# openThermostatShield.net
KiCad netlist of a schematic drawn in EAGLE
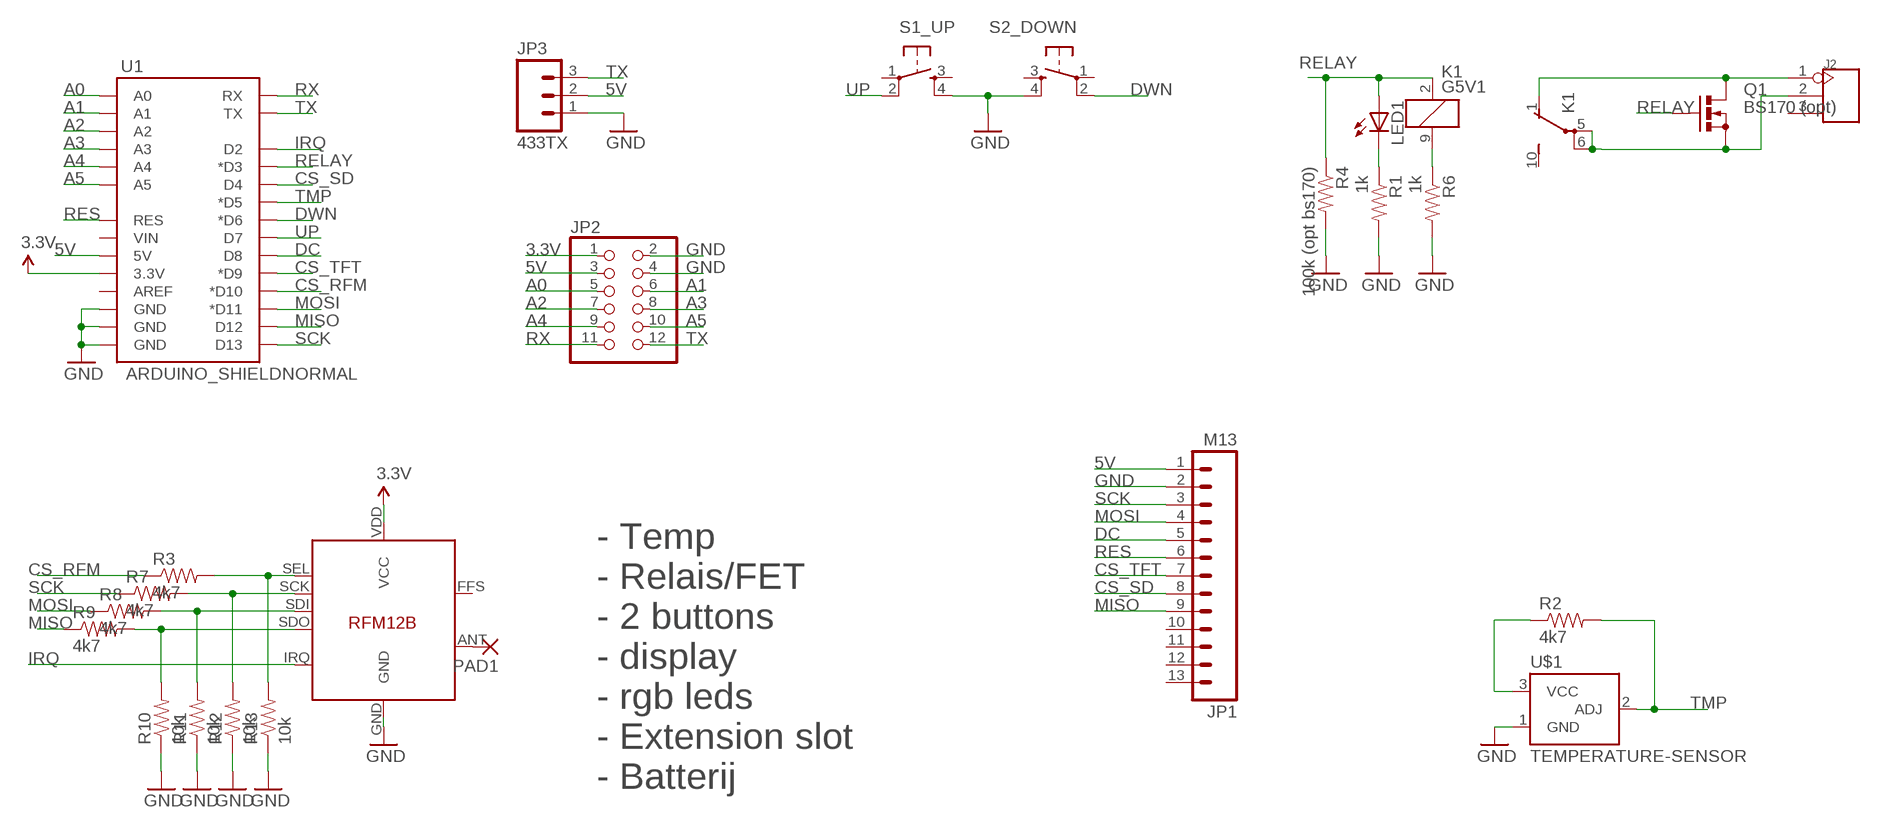
[diagram p0: schematic, sheet 1]

(export (version "E")
  (design (tool "Eeschema 10.0.6"))
  (components
    (comp (ref "J2")
      (value "SCREW-TERMINAL-3P'5.08'")
      (footprint "eagle-import:3P-5.08")
      (libsource (lib "eagle-import") (part "SCREW-TERMINAL-3P'5.08'"))
    )
    (comp (ref "JP1")
      (value "M13")
      (footprint "eagle-import:1X13")
      (libsource (lib "eagle-import") (part "M13"))
    )
    (comp (ref "JP2")
      (value "PINHD-2X6/90")
      (footprint "eagle-import:2X06_90")
      (libsource (lib "eagle-import") (part "PINHD-2X6/90"))
    )
    (comp (ref "JP3")
      (value "433TX")
      (footprint "eagle-import:MOLEX-1X3")
      (libsource (lib "eagle-import") (part "M03POLAR"))
    )
    (comp (ref "K1")
      (value "G5V1")
      (footprint "eagle-import:G5V1")
      (fields (field (name "MPN") "G5V-1-DC24"))
      (libsource (lib "eagle-import") (part "G5V1"))
    )
    (comp (ref "LED1")
      (value "LED-3MM-NO_SILK")
      (footprint "eagle-import:LED3MM-NS")
      (libsource (lib "eagle-import") (part "LED-3MM-NO_SILK"))
    )
    (comp (ref "PAD1")
      (value "1,6/0,8")
      (footprint "eagle-import:1,6_0,8")
      (libsource (lib "eagle-import") (part "1,6/0,8"))
    )
    (comp (ref "Q1")
      (value "BS170 (opt)")
      (footprint "eagle-import:SOT54E")
      (libsource (lib "eagle-import") (part "BS170"))
    )
    (comp (ref "R1")
      (value "1k")
      (footprint "eagle-import:AXIAL-0.3")
      (libsource (lib "eagle-import") (part "RESISTORAXIAL-0.3"))
    )
    (comp (ref "R2")
      (value "4k7")
      (footprint "eagle-import:AXIAL-0.3")
      (libsource (lib "eagle-import") (part "RESISTORAXIAL-0.3"))
    )
    (comp (ref "R3")
      (value "4k7")
      (footprint "eagle-import:AXIAL-0.3")
      (libsource (lib "eagle-import") (part "RESISTORAXIAL-0.3"))
    )
    (comp (ref "R4")
      (value "100k (opt bs170)")
      (footprint "eagle-import:AXIAL-0.3")
      (libsource (lib "eagle-import") (part "RESISTORAXIAL-0.3"))
    )
    (comp (ref "R6")
      (value "1k")
      (footprint "eagle-import:AXIAL-0.3")
      (libsource (lib "eagle-import") (part "RESISTORAXIAL-0.3"))
    )
    (comp (ref "R7")
      (value "4k7")
      (footprint "eagle-import:AXIAL-0.3")
      (libsource (lib "eagle-import") (part "RESISTORAXIAL-0.3"))
    )
    (comp (ref "R8")
      (value "4k7")
      (footprint "eagle-import:AXIAL-0.3")
      (libsource (lib "eagle-import") (part "RESISTORAXIAL-0.3"))
    )
    (comp (ref "R9")
      (value "4k7")
      (footprint "eagle-import:AXIAL-0.3")
      (libsource (lib "eagle-import") (part "RESISTORAXIAL-0.3"))
    )
    (comp (ref "R10")
      (value "10k")
      (footprint "eagle-import:AXIAL-0.3")
      (libsource (lib "eagle-import") (part "RESISTORAXIAL-0.3"))
    )
    (comp (ref "R11")
      (value "10k")
      (footprint "eagle-import:AXIAL-0.3")
      (libsource (lib "eagle-import") (part "RESISTORAXIAL-0.3"))
    )
    (comp (ref "R12")
      (value "10k")
      (footprint "eagle-import:AXIAL-0.3")
      (libsource (lib "eagle-import") (part "RESISTORAXIAL-0.3"))
    )
    (comp (ref "R13")
      (value "10k")
      (footprint "eagle-import:AXIAL-0.3")
      (libsource (lib "eagle-import") (part "RESISTORAXIAL-0.3"))
    )
    (comp (ref "S1_UP")
      (value "TAC_SWITCHPTH")
      (footprint "eagle-import:TACTILE-PTH")
      (libsource (lib "eagle-import") (part "TAC_SWITCHPTH"))
    )
    (comp (ref "S2_DOWN")
      (value "TAC_SWITCHPTH")
      (footprint "eagle-import:TACTILE-PTH")
      (libsource (lib "eagle-import") (part "TAC_SWITCHPTH"))
    )
    (comp (ref "U$1")
      (value "TEMPERATURE-SENSOR")
      (footprint "eagle-import:TO-92")
      (libsource (lib "eagle-import") (part "TEMPERATURE-SENSOR"))
    )
    (comp (ref "U$2")
      (value "RFM12B")
      (footprint "eagle-import:RFM12B")
      (libsource (lib "eagle-import") (part "RFM12B"))
    )
    (comp (ref "U1")
      (value "ARDUINO_SHIELDNORMAL")
      (footprint "eagle-import:DUEMILANOVE_SHIELD_5X5")
      (libsource (lib "eagle-import") (part "ARDUINO_SHIELDNORMAL"))
    )
  )
  (nets
    (net (code "1") (name "/5V") (class "Default")
      (node (ref "JP1") (pin "1") (pinfunction "1_1") (pintype "passive"))
      (node (ref "JP2") (pin "3") (pinfunction "3_3") (pintype "passive"))
      (node (ref "JP3") (pin "2") (pinfunction "2_2") (pintype "passive"))
      (node (ref "U1") (pin "5V") (pinfunction "5V_5V") (pintype "bidirectional"))
    )
    (net (code "2") (name "/A0") (class "Default")
      (node (ref "JP2") (pin "5") (pinfunction "5_5") (pintype "passive"))
      (node (ref "U1") (pin "A0") (pinfunction "A0_A0") (pintype "bidirectional"))
    )
    (net (code "3") (name "/A1") (class "Default")
      (node (ref "JP2") (pin "6") (pinfunction "6_6") (pintype "passive"))
      (node (ref "U1") (pin "A1") (pinfunction "A1_A1") (pintype "bidirectional"))
    )
    (net (code "4") (name "/A2") (class "Default")
      (node (ref "JP2") (pin "7") (pinfunction "7_7") (pintype "passive"))
      (node (ref "U1") (pin "A2") (pinfunction "A2_A2") (pintype "bidirectional"))
    )
    (net (code "5") (name "/A3") (class "Default")
      (node (ref "JP2") (pin "8") (pinfunction "8_8") (pintype "passive"))
      (node (ref "U1") (pin "A3") (pinfunction "A3_A3") (pintype "bidirectional"))
    )
    (net (code "6") (name "/A4") (class "Default")
      (node (ref "JP2") (pin "9") (pinfunction "9_9") (pintype "passive"))
      (node (ref "U1") (pin "A4") (pinfunction "A4_A4") (pintype "bidirectional"))
    )
    (net (code "7") (name "/A5") (class "Default")
      (node (ref "JP2") (pin "10") (pinfunction "10_10") (pintype "passive"))
      (node (ref "U1") (pin "A5") (pinfunction "A5_A5") (pintype "bidirectional"))
    )
    (net (code "8") (name "/CS_RFM") (class "Default")
      (node (ref "R3") (pin "P$1") (pinfunction "1_P$1") (pintype "passive"))
      (node (ref "U1") (pin "D10") (pinfunction "*D10_D10") (pintype "bidirectional"))
    )
    (net (code "9") (name "/CS_SD") (class "Default")
      (node (ref "JP1") (pin "8") (pinfunction "8_8") (pintype "passive"))
      (node (ref "U1") (pin "D4") (pinfunction "D4_D4") (pintype "bidirectional"))
    )
    (net (code "10") (name "/CS_TFT") (class "Default")
      (node (ref "JP1") (pin "7") (pinfunction "7_7") (pintype "passive"))
      (node (ref "U1") (pin "D9") (pinfunction "*D9_D9") (pintype "bidirectional"))
    )
    (net (code "11") (name "/DC") (class "Default")
      (node (ref "JP1") (pin "5") (pinfunction "5_5") (pintype "passive"))
      (node (ref "U1") (pin "D8") (pinfunction "D8_D8") (pintype "bidirectional"))
    )
    (net (code "12") (name "/DWN") (class "Default")
      (node (ref "S2_DOWN") (pin "2") (pinfunction "2_2") (pintype "passive"))
      (node (ref "U1") (pin "D6") (pinfunction "*D6_D6") (pintype "bidirectional"))
    )
    (net (code "13") (name "/IRQ") (class "Default")
      (node (ref "U$2") (pin "IRQ") (pinfunction "IRQ_IRQ") (pintype "open_collector"))
      (node (ref "U1") (pin "D2") (pinfunction "D2_D2") (pintype "bidirectional"))
    )
    (net (code "14") (name "/MISO") (class "Default")
      (node (ref "JP1") (pin "9") (pinfunction "9_9") (pintype "passive"))
      (node (ref "R9") (pin "P$1") (pinfunction "1_P$1") (pintype "passive"))
      (node (ref "U1") (pin "D12") (pinfunction "D12_D12") (pintype "bidirectional"))
    )
    (net (code "15") (name "/MOSI") (class "Default")
      (node (ref "JP1") (pin "4") (pinfunction "4_4") (pintype "passive"))
      (node (ref "R8") (pin "P$1") (pinfunction "1_P$1") (pintype "passive"))
      (node (ref "U1") (pin "D11") (pinfunction "*D11_D11") (pintype "bidirectional"))
    )
    (net (code "16") (name "/RELAY") (class "Default")
      (node (ref "K1") (pin "2") (pinfunction "1_2") (pintype "passive"))
      (node (ref "LED1") (pin "A") (pinfunction "A_A") (pintype "passive"))
      (node (ref "Q1") (pin "G") (pinfunction "G_G") (pintype "passive"))
      (node (ref "R4") (pin "P$1") (pinfunction "1_P$1") (pintype "passive"))
      (node (ref "U1") (pin "D3") (pinfunction "*D3_D3") (pintype "bidirectional"))
    )
    (net (code "17") (name "/RES") (class "Default")
      (node (ref "JP1") (pin "6") (pinfunction "6_6") (pintype "passive"))
      (node (ref "U1") (pin "RES") (pinfunction "RES_RES") (pintype "bidirectional"))
    )
    (net (code "18") (name "/RX") (class "Default")
      (node (ref "JP2") (pin "11") (pinfunction "11_11") (pintype "passive"))
      (node (ref "U1") (pin "RX") (pinfunction "RX_RX") (pintype "bidirectional"))
    )
    (net (code "19") (name "/SCK") (class "Default")
      (node (ref "JP1") (pin "3") (pinfunction "3_3") (pintype "passive"))
      (node (ref "R7") (pin "P$1") (pinfunction "1_P$1") (pintype "passive"))
      (node (ref "U1") (pin "D13") (pinfunction "D13_D13") (pintype "bidirectional"))
    )
    (net (code "20") (name "/TMP") (class "Default")
      (node (ref "R2") (pin "P$2") (pinfunction "2_P$2") (pintype "passive"))
      (node (ref "U$1") (pin "2") (pinfunction "ADJ_2") (pintype "bidirectional"))
      (node (ref "U1") (pin "D5") (pinfunction "*D5_D5") (pintype "bidirectional"))
    )
    (net (code "21") (name "/TX") (class "Default")
      (node (ref "JP2") (pin "12") (pinfunction "12_12") (pintype "passive"))
      (node (ref "JP3") (pin "3") (pinfunction "3_3") (pintype "passive"))
      (node (ref "U1") (pin "TX") (pinfunction "TX_TX") (pintype "bidirectional"))
    )
    (net (code "22") (name "/UP") (class "Default")
      (node (ref "S1_UP") (pin "2") (pinfunction "2_2") (pintype "passive"))
      (node (ref "U1") (pin "D7") (pinfunction "D7_D7") (pintype "bidirectional"))
    )
    (net (code "23") (name "3.3V") (class "Default")
      (node (ref "JP2") (pin "1") (pinfunction "1_1") (pintype "passive"))
      (node (ref "U$2") (pin "VDD") (pinfunction "VCC_VDD") (pintype "power_in"))
      (node (ref "U1") (pin "3.3V") (pinfunction "3.3V_3.3V") (pintype "bidirectional"))
    )
    (net (code "24") (name "GND") (class "Default")
      (node (ref "JP1") (pin "2") (pinfunction "2_2") (pintype "passive"))
      (node (ref "JP2") (pin "2") (pinfunction "2_2") (pintype "passive"))
      (node (ref "JP2") (pin "4") (pinfunction "4_4") (pintype "passive"))
      (node (ref "JP3") (pin "1") (pinfunction "1_1") (pintype "passive"))
      (node (ref "R1") (pin "P$2") (pinfunction "2_P$2") (pintype "passive"))
      (node (ref "R10") (pin "P$1") (pinfunction "1_P$1") (pintype "passive"))
      (node (ref "R11") (pin "P$1") (pinfunction "1_P$1") (pintype "passive"))
      (node (ref "R12") (pin "P$1") (pinfunction "1_P$1") (pintype "passive"))
      (node (ref "R13") (pin "P$1") (pinfunction "1_P$1") (pintype "passive"))
      (node (ref "R4") (pin "P$2") (pinfunction "2_P$2") (pintype "passive"))
      (node (ref "R6") (pin "P$2") (pinfunction "2_P$2") (pintype "passive"))
      (node (ref "S1_UP") (pin "4") (pinfunction "4_4") (pintype "passive"))
      (node (ref "S2_DOWN") (pin "4") (pinfunction "4_4") (pintype "passive"))
      (node (ref "U$1") (pin "1") (pinfunction "GND_1") (pintype "bidirectional"))
      (node (ref "U$2") (pin "GND") (pinfunction "GND_GND") (pintype "power_in"))
      (node (ref "U1") (pin "GND@0") (pinfunction "GND_GND@0") (pintype "bidirectional"))
      (node (ref "U1") (pin "GND@1") (pinfunction "GND_GND@1") (pintype "bidirectional"))
      (node (ref "U1") (pin "GND@2") (pinfunction "GND_GND@2") (pintype "bidirectional"))
    )
    (net (code "25") (name "Net-(J2-P$1)") (class "Default")
      (node (ref "J2") (pin "1") (pinfunction "P$1_1") (pintype "bidirectional"))
      (node (ref "K1") (pin "1") (pinfunction "O_1") (pintype "passive"))
      (node (ref "Q1") (pin "D") (pinfunction "D_D") (pintype "passive"))
    )
    (net (code "26") (name "Net-(J2-P$2)") (class "Default")
      (node (ref "J2") (pin "2") (pinfunction "P$2_2") (pintype "bidirectional"))
      (node (ref "K1") (pin "5") (pinfunction "P_5") (pintype "passive"))
      (node (ref "K1") (pin "6") (pinfunction "P_6") (pintype "passive"))
      (node (ref "Q1") (pin "S") (pinfunction "S_S") (pintype "passive"))
    )
    (net (code "27") (name "Net-(K1A-2)") (class "Default")
      (node (ref "K1") (pin "9") (pinfunction "2_9") (pintype "passive"))
      (node (ref "R6") (pin "P$1") (pinfunction "1_P$1") (pintype "passive"))
    )
    (net (code "28") (name "Net-(LED1-C)") (class "Default")
      (node (ref "LED1") (pin "K") (pinfunction "C_K") (pintype "passive"))
      (node (ref "R1") (pin "P$1") (pinfunction "1_P$1") (pintype "passive"))
    )
    (net (code "29") (name "Net-(PAD1-P)") (class "Default")
      (node (ref "PAD1") (pin "1") (pinfunction "P_1") (pintype "passive"))
      (node (ref "U$2") (pin "ANT") (pinfunction "ANT_ANT") (pintype "passive"))
    )
    (net (code "30") (name "Net-(R2-1)") (class "Default")
      (node (ref "R2") (pin "P$1") (pinfunction "1_P$1") (pintype "passive"))
      (node (ref "U$1") (pin "3") (pinfunction "VCC_3") (pintype "bidirectional"))
    )
    (net (code "31") (name "Net-(R10-2)") (class "Default")
      (node (ref "R10") (pin "P$2") (pinfunction "2_P$2") (pintype "passive"))
      (node (ref "R9") (pin "P$2") (pinfunction "2_P$2") (pintype "passive"))
      (node (ref "U$2") (pin "SDO") (pinfunction "SDO_SDO") (pintype "output"))
    )
    (net (code "32") (name "Net-(R11-2)") (class "Default")
      (node (ref "R11") (pin "P$2") (pinfunction "2_P$2") (pintype "passive"))
      (node (ref "R8") (pin "P$2") (pinfunction "2_P$2") (pintype "passive"))
      (node (ref "U$2") (pin "SDI") (pinfunction "SDI_SDI") (pintype "input"))
    )
    (net (code "33") (name "Net-(R12-2)") (class "Default")
      (node (ref "R12") (pin "P$2") (pinfunction "2_P$2") (pintype "passive"))
      (node (ref "R7") (pin "P$2") (pinfunction "2_P$2") (pintype "passive"))
      (node (ref "U$2") (pin "SCK") (pinfunction "SCK_SCK") (pintype "input"))
    )
    (net (code "34") (name "Net-(R13-2)") (class "Default")
      (node (ref "R13") (pin "P$2") (pinfunction "2_P$2") (pintype "passive"))
      (node (ref "R3") (pin "P$2") (pinfunction "2_P$2") (pintype "passive"))
      (node (ref "U$2") (pin "SEL") (pinfunction "SEL_SEL") (pintype "input"))
    )
    (net (code "35") (name "unconnected-(J2-P$3-Pad3)") (class "Default")
      (node (ref "J2") (pin "3") (pinfunction "P$3_3") (pintype "bidirectional"))
    )
    (net (code "36") (name "unconnected-(JP1-Pad10)") (class "Default")
      (node (ref "JP1") (pin "10") (pinfunction "10_10") (pintype "passive"))
    )
    (net (code "37") (name "unconnected-(JP1-Pad11)") (class "Default")
      (node (ref "JP1") (pin "11") (pinfunction "11_11") (pintype "passive"))
    )
    (net (code "38") (name "unconnected-(JP1-Pad12)") (class "Default")
      (node (ref "JP1") (pin "12") (pinfunction "12_12") (pintype "passive"))
    )
    (net (code "39") (name "unconnected-(JP1-Pad13)") (class "Default")
      (node (ref "JP1") (pin "13") (pinfunction "13_13") (pintype "passive"))
    )
    (net (code "40") (name "unconnected-(K1B-S-Pad10)") (class "Default")
      (node (ref "K1") (pin "10") (pinfunction "S_10") (pintype "passive"))
    )
    (net (code "41") (name "unconnected-(S1_UP-Pad1)") (class "Default")
      (node (ref "S1_UP") (pin "1") (pinfunction "1_1") (pintype "passive"))
    )
    (net (code "42") (name "unconnected-(S1_UP-Pad3)") (class "Default")
      (node (ref "S1_UP") (pin "3") (pinfunction "3_3") (pintype "passive"))
    )
    (net (code "43") (name "unconnected-(S2_DOWN-Pad1)") (class "Default")
      (node (ref "S2_DOWN") (pin "1") (pinfunction "1_1") (pintype "passive"))
    )
    (net (code "44") (name "unconnected-(S2_DOWN-Pad3)") (class "Default")
      (node (ref "S2_DOWN") (pin "3") (pinfunction "3_3") (pintype "passive"))
    )
    (net (code "45") (name "unconnected-(U$2-PadFFS)") (class "Default")
      (node (ref "U$2") (pin "FFS") (pinfunction "FFS_FFS") (pintype "bidirectional"))
    )
    (net (code "46") (name "unconnected-(U1-PadAREF)") (class "Default")
      (node (ref "U1") (pin "AREF") (pinfunction "AREF_AREF") (pintype "bidirectional"))
    )
    (net (code "47") (name "unconnected-(U1-PadVIN)") (class "Default")
      (node (ref "U1") (pin "VIN") (pinfunction "VIN_VIN") (pintype "bidirectional"))
    )
  )
)
